# zara.net
KiCad netlist of a schematic drawn in Altium Designer
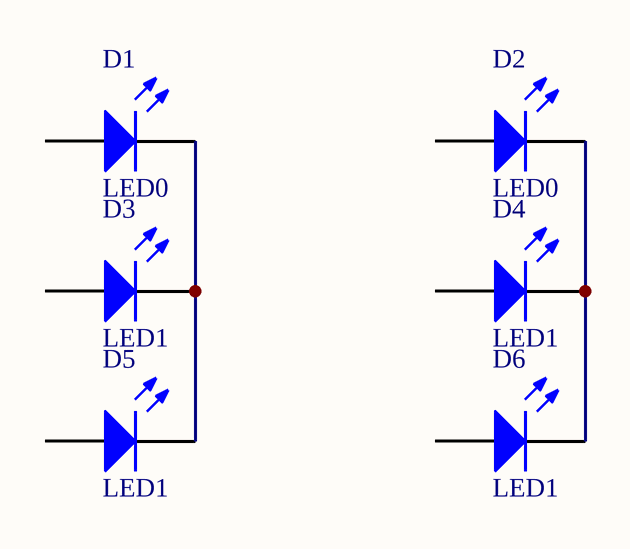
[diagram p0: zara.SchDoc]

(export (version "E")
  (design (tool "Eeschema 10.0.6"))
  (components
    (comp (ref "D1")
      (value "LED0")
      (footprint "LED-0")
      (description "Typical INFRARED GaAs LED")
      (fields (field (name "PUBLISHER") "Altium Limited"))
      (libsource (lib "Miscellaneous Devices") (part "LED0"))
    )
    (comp (ref "D2")
      (value "LED0")
      (footprint "LED-0")
      (description "Typical INFRARED GaAs LED")
      (fields (field (name "PUBLISHER") "Altium Limited"))
      (libsource (lib "Miscellaneous Devices") (part "LED0"))
    )
    (comp (ref "D3")
      (value "LED1")
      (footprint "LED-1")
      (description "Typical RED GaAs LED")
      (fields (field (name "PUBLISHER") "Altium Limited"))
      (libsource (lib "Miscellaneous Devices") (part "LED1"))
    )
    (comp (ref "D4")
      (value "LED1")
      (footprint "LED-1")
      (description "Typical RED GaAs LED")
      (fields (field (name "PUBLISHER") "Altium Limited"))
      (libsource (lib "Miscellaneous Devices") (part "LED1"))
    )
    (comp (ref "D5")
      (value "LED1")
      (footprint "LED-1")
      (description "Typical RED GaAs LED")
      (fields (field (name "PUBLISHER") "Altium Limited"))
      (libsource (lib "Miscellaneous Devices") (part "LED1"))
    )
    (comp (ref "D6")
      (value "LED1")
      (footprint "LED-1")
      (description "Typical RED GaAs LED")
      (fields (field (name "PUBLISHER") "Altium Limited"))
      (libsource (lib "Miscellaneous Devices") (part "LED1"))
    )
  )
  (nets
    (net (code "1") (name "Net-(D1-K)") (class "Default")
      (node (ref "D1") (pin "2") (pinfunction "K_2") (pintype "passive"))
      (node (ref "D3") (pin "2") (pinfunction "K_2") (pintype "passive"))
      (node (ref "D5") (pin "2") (pinfunction "K_2") (pintype "passive"))
    )
    (net (code "2") (name "Net-(D2-K)") (class "Default")
      (node (ref "D2") (pin "2") (pinfunction "K_2") (pintype "passive"))
      (node (ref "D4") (pin "2") (pinfunction "K_2") (pintype "passive"))
      (node (ref "D6") (pin "2") (pinfunction "K_2") (pintype "passive"))
    )
    (net (code "3") (name "unconnected-(D1-A-Pad1)") (class "Default")
      (node (ref "D1") (pin "1") (pinfunction "A_1") (pintype "passive"))
    )
    (net (code "4") (name "unconnected-(D2-A-Pad1)") (class "Default")
      (node (ref "D2") (pin "1") (pinfunction "A_1") (pintype "passive"))
    )
    (net (code "5") (name "unconnected-(D3-A-Pad1)") (class "Default")
      (node (ref "D3") (pin "1") (pinfunction "A_1") (pintype "passive"))
    )
    (net (code "6") (name "unconnected-(D4-A-Pad1)") (class "Default")
      (node (ref "D4") (pin "1") (pinfunction "A_1") (pintype "passive"))
    )
    (net (code "7") (name "unconnected-(D5-A-Pad1)") (class "Default")
      (node (ref "D5") (pin "1") (pinfunction "A_1") (pintype "passive"))
    )
    (net (code "8") (name "unconnected-(D6-A-Pad1)") (class "Default")
      (node (ref "D6") (pin "1") (pinfunction "A_1") (pintype "passive"))
    )
  )
)
